# ffs_no_amp.net
KiCad netlist of a schematic drawn in EAGLE
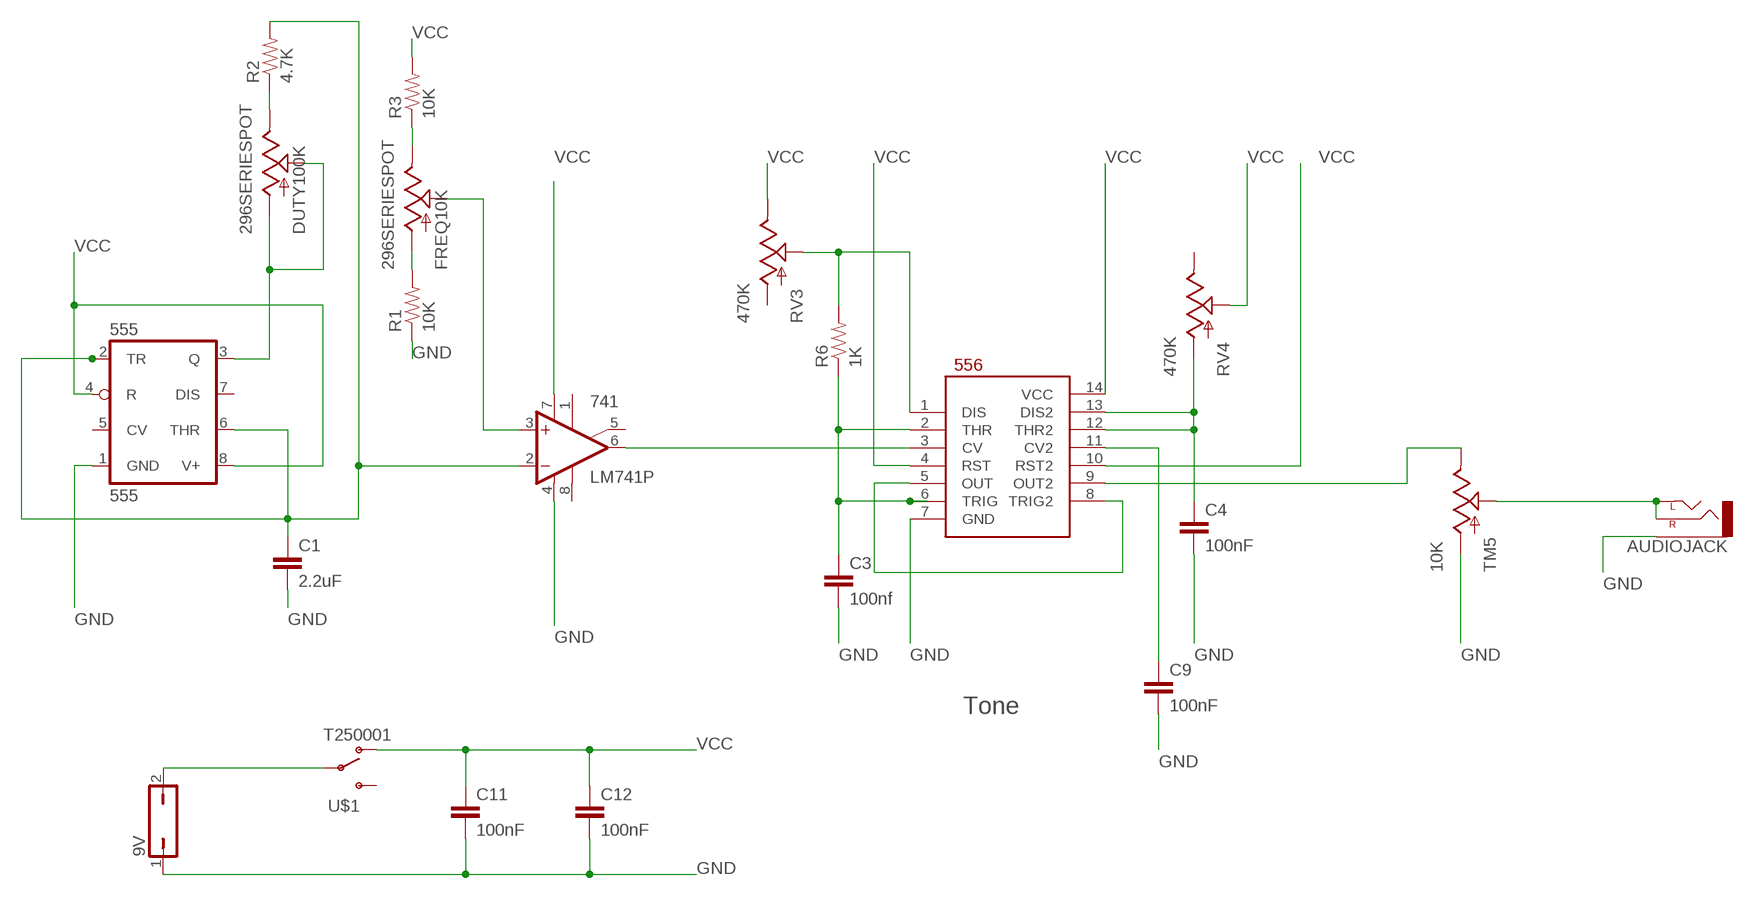
[diagram p0: schematic, sheet 1]

(export (version "E")
  (design (tool "Eeschema 10.0.6"))
  (components
    (comp (ref "9V")
      (value "JP1Q")
      (footprint "eagle-import:JP1")
      (libsource (lib "eagle-import") (part "JP1Q"))
    )
    (comp (ref "555")
      (value "555")
      (footprint "eagle-import:DIL08-ROUND")
      (libsource (lib "eagle-import") (part "555NLM"))
    )
    (comp (ref "556")
      (value "556")
      (footprint "eagle-import:DIL14")
      (libsource (lib "eagle-import") (part "556"))
    )
    (comp (ref "741")
      (value "LM741P")
      (footprint "eagle-import:DIL08")
      (libsource (lib "eagle-import") (part "741PLM"))
    )
    (comp (ref "AUDIOJACK")
      (value "AUDIO-JACKPTH")
      (footprint "eagle-import:AUDIO-JACK")
      (libsource (lib "eagle-import") (part "AUDIO-JACKPTH"))
    )
    (comp (ref "C1")
      (value "2.2uF")
      (footprint "eagle-import:CAP-PTH-5MM")
      (libsource (lib "eagle-import") (part "CAPPTH1"))
    )
    (comp (ref "C3")
      (value "100nf")
      (footprint "eagle-import:CAP-PTH-SMALL")
      (libsource (lib "eagle-import") (part "CAPPTH"))
    )
    (comp (ref "C4")
      (value "100nF")
      (footprint "eagle-import:CAP-PTH-SMALL")
      (libsource (lib "eagle-import") (part "CAPPTH"))
    )
    (comp (ref "C9")
      (value "100nF")
      (footprint "eagle-import:CAP-PTH-SMALL")
      (libsource (lib "eagle-import") (part "CAPPTH"))
    )
    (comp (ref "C11")
      (value "100nF")
      (footprint "eagle-import:CAP-PTH-SMALL")
      (libsource (lib "eagle-import") (part "CAPPTH"))
    )
    (comp (ref "C12")
      (value "100nF")
      (footprint "eagle-import:CAP-PTH-SMALL")
      (libsource (lib "eagle-import") (part "CAPPTH"))
    )
    (comp (ref "DUTY100K")
      (value "296SERIESPOT")
      (footprint "eagle-import:296SERIESPOT")
      (libsource (lib "eagle-import") (part "296SERIESPOT"))
    )
    (comp (ref "FREQ10K")
      (value "296SERIESPOT")
      (footprint "eagle-import:296SERIESPOT")
      (libsource (lib "eagle-import") (part "296SERIESPOT"))
    )
    (comp (ref "R1")
      (value "10K")
      (footprint "eagle-import:AXIAL-0.4")
      (libsource (lib "eagle-import") (part "SparkFun-Resistors_RESISTORPTH-1/4W"))
    )
    (comp (ref "R2")
      (value "4.7K")
      (footprint "eagle-import:AXIAL-0.4")
      (libsource (lib "eagle-import") (part "SparkFun-Resistors_RESISTORPTH-1/4W"))
    )
    (comp (ref "R3")
      (value "10K")
      (footprint "eagle-import:AXIAL-0.4")
      (libsource (lib "eagle-import") (part "SparkFun-Resistors_RESISTORPTH-1/4W"))
    )
    (comp (ref "R6")
      (value "1K")
      (footprint "eagle-import:AXIAL-0.4")
      (libsource (lib "eagle-import") (part "RESISTORPTH-1/4W"))
    )
    (comp (ref "RV3")
      (value "470K")
      (footprint "eagle-import:296SERIESPOT")
      (libsource (lib "eagle-import") (part "296SERIESPOT"))
    )
    (comp (ref "RV4")
      (value "470K")
      (footprint "eagle-import:296SERIESPOT")
      (libsource (lib "eagle-import") (part "296SERIESPOT"))
    )
    (comp (ref "TM5")
      (value "10K")
      (footprint "eagle-import:296SERIESPOT")
      (libsource (lib "eagle-import") (part "296SERIESPOT"))
    )
    (comp (ref "U$1")
      (value "T250001")
      (footprint "eagle-import:T250001")
      (libsource (lib "eagle-import") (part "T250001"))
    )
  )
  (nets
    (net (code "1") (name "/GND") (class "Default")
      (node (ref "555") (pin "1") (pinfunction "GND_1") (pintype "power_in"))
      (node (ref "556") (pin "7") (pinfunction "GND_7") (pintype "bidirectional"))
      (node (ref "741") (pin "4") (pinfunction "V-_4") (pintype "power_in"))
      (node (ref "9V") (pin "1") (pinfunction "1_1") (pintype "passive"))
      (node (ref "AUDIOJACK") (pin "SLEEVE") (pinfunction "SLEEVE_SLEEVE") (pintype "bidirectional"))
      (node (ref "C1") (pin "2") (pinfunction "2_2") (pintype "passive"))
      (node (ref "C11") (pin "2") (pinfunction "2_2") (pintype "passive"))
      (node (ref "C12") (pin "2") (pinfunction "2_2") (pintype "passive"))
      (node (ref "C3") (pin "2") (pinfunction "2_2") (pintype "passive"))
      (node (ref "C4") (pin "2") (pinfunction "2_2") (pintype "passive"))
      (node (ref "C9") (pin "2") (pinfunction "2_2") (pintype "passive"))
      (node (ref "R1") (pin "P$1") (pinfunction "1_P$1") (pintype "passive"))
      (node (ref "TM5") (pin "PIN1") (pinfunction "A_PIN1") (pintype "passive"))
    )
    (net (code "2") (name "/VCC") (class "Default")
      (node (ref "555") (pin "4") (pinfunction "R_4") (pintype "input"))
      (node (ref "555") (pin "8") (pinfunction "V+_8") (pintype "power_in"))
      (node (ref "556") (pin "10") (pinfunction "RST2_10") (pintype "bidirectional"))
      (node (ref "556") (pin "14") (pinfunction "VCC_14") (pintype "bidirectional"))
      (node (ref "556") (pin "4") (pinfunction "RST_4") (pintype "bidirectional"))
      (node (ref "741") (pin "7") (pinfunction "V+_7") (pintype "power_in"))
      (node (ref "C11") (pin "1") (pinfunction "1_1") (pintype "passive"))
      (node (ref "C12") (pin "1") (pinfunction "1_1") (pintype "passive"))
      (node (ref "R3") (pin "P$2") (pinfunction "2_P$2") (pintype "passive"))
      (node (ref "RV3") (pin "PIN3") (pinfunction "E_PIN3") (pintype "passive"))
      (node (ref "RV4") (pin "PIN2") (pinfunction "S_PIN2") (pintype "passive"))
      (node (ref "U$1") (pin "4") (pinfunction "O_4") (pintype "passive"))
    )
    (net (code "3") (name "Net-(555-Q)") (class "Default")
      (node (ref "555") (pin "3") (pinfunction "Q_3") (pintype "output"))
      (node (ref "DUTY100K") (pin "PIN1") (pinfunction "A_PIN1") (pintype "passive"))
      (node (ref "DUTY100K") (pin "PIN2") (pinfunction "S_PIN2") (pintype "passive"))
    )
    (net (code "4") (name "Net-(555-THR)") (class "Default")
      (node (ref "555") (pin "2") (pinfunction "TR_2") (pintype "input"))
      (node (ref "555") (pin "6") (pinfunction "THR_6") (pintype "input"))
      (node (ref "741") (pin "2") (pinfunction "-IN_2") (pintype "input"))
      (node (ref "C1") (pin "1") (pinfunction "1_1") (pintype "passive"))
      (node (ref "R2") (pin "P$2") (pinfunction "2_P$2") (pintype "passive"))
    )
    (net (code "5") (name "Net-(556-CV)") (class "Default")
      (node (ref "556") (pin "3") (pinfunction "CV_3") (pintype "bidirectional"))
      (node (ref "741") (pin "6") (pinfunction "OUT_6") (pintype "output"))
    )
    (net (code "6") (name "Net-(556-CV2)") (class "Default")
      (node (ref "556") (pin "11") (pinfunction "CV2_11") (pintype "bidirectional"))
      (node (ref "C9") (pin "1") (pinfunction "1_1") (pintype "passive"))
    )
    (net (code "7") (name "Net-(556-DIS)") (class "Default")
      (node (ref "556") (pin "1") (pinfunction "DIS_1") (pintype "bidirectional"))
      (node (ref "R6") (pin "P$2") (pinfunction "2_P$2") (pintype "passive"))
      (node (ref "RV3") (pin "PIN2") (pinfunction "S_PIN2") (pintype "passive"))
    )
    (net (code "8") (name "Net-(556-DIS2)") (class "Default")
      (node (ref "556") (pin "12") (pinfunction "THR2_12") (pintype "bidirectional"))
      (node (ref "556") (pin "13") (pinfunction "DIS2_13") (pintype "bidirectional"))
      (node (ref "C4") (pin "1") (pinfunction "1_1") (pintype "passive"))
      (node (ref "RV4") (pin "PIN1") (pinfunction "A_PIN1") (pintype "passive"))
    )
    (net (code "9") (name "Net-(556-OUT)") (class "Default")
      (node (ref "556") (pin "5") (pinfunction "OUT_5") (pintype "bidirectional"))
      (node (ref "556") (pin "8") (pinfunction "TRIG2_8") (pintype "bidirectional"))
    )
    (net (code "10") (name "Net-(556-OUT2)") (class "Default")
      (node (ref "556") (pin "9") (pinfunction "OUT2_9") (pintype "bidirectional"))
      (node (ref "TM5") (pin "PIN3") (pinfunction "E_PIN3") (pintype "passive"))
    )
    (net (code "11") (name "Net-(556-THR)") (class "Default")
      (node (ref "556") (pin "2") (pinfunction "THR_2") (pintype "bidirectional"))
      (node (ref "556") (pin "6") (pinfunction "TRIG_6") (pintype "bidirectional"))
      (node (ref "C3") (pin "1") (pinfunction "1_1") (pintype "passive"))
      (node (ref "R6") (pin "P$1") (pinfunction "1_P$1") (pintype "passive"))
    )
    (net (code "12") (name "Net-(741-+IN)") (class "Default")
      (node (ref "741") (pin "3") (pinfunction "+IN_3") (pintype "input"))
      (node (ref "FREQ10K") (pin "PIN2") (pinfunction "S_PIN2") (pintype "passive"))
    )
    (net (code "13") (name "Net-(AUDIOJACK-LEFT)") (class "Default")
      (node (ref "AUDIOJACK") (pin "RING") (pinfunction "RIGHT_RING") (pintype "bidirectional"))
      (node (ref "AUDIOJACK") (pin "TIP") (pinfunction "LEFT_TIP") (pintype "bidirectional"))
      (node (ref "TM5") (pin "PIN2") (pinfunction "S_PIN2") (pintype "passive"))
    )
    (net (code "14") (name "Net-(DUTY100K-E)") (class "Default")
      (node (ref "DUTY100K") (pin "PIN3") (pinfunction "E_PIN3") (pintype "passive"))
      (node (ref "R2") (pin "P$1") (pinfunction "1_P$1") (pintype "passive"))
    )
    (net (code "15") (name "Net-(FREQ10K-A)") (class "Default")
      (node (ref "FREQ10K") (pin "PIN1") (pinfunction "A_PIN1") (pintype "passive"))
      (node (ref "R1") (pin "P$2") (pinfunction "2_P$2") (pintype "passive"))
    )
    (net (code "16") (name "Net-(FREQ10K-E)") (class "Default")
      (node (ref "FREQ10K") (pin "PIN3") (pinfunction "E_PIN3") (pintype "passive"))
      (node (ref "R3") (pin "P$1") (pinfunction "1_P$1") (pintype "passive"))
    )
    (net (code "17") (name "Net-(U$1-P)") (class "Default")
      (node (ref "9V") (pin "2") (pinfunction "2_2") (pintype "passive"))
      (node (ref "U$1") (pin "5") (pinfunction "P_5") (pintype "passive"))
    )
    (net (code "18") (name "unconnected-(555-CV-Pad5)") (class "Default")
      (node (ref "555") (pin "5") (pinfunction "CV_5") (pintype "input"))
    )
    (net (code "19") (name "unconnected-(555-DIS-Pad7)") (class "Default")
      (node (ref "555") (pin "7") (pinfunction "DIS_7") (pintype "input"))
    )
    (net (code "20") (name "unconnected-(741-ON1-Pad1)") (class "Default")
      (node (ref "741") (pin "1") (pinfunction "ON1_1") (pintype "passive"))
    )
    (net (code "21") (name "unconnected-(741-ON2-Pad5)") (class "Default")
      (node (ref "741") (pin "5") (pinfunction "ON2_5") (pintype "passive"))
    )
    (net (code "22") (name "unconnected-(741-OPT-Pad8)") (class "Default")
      (node (ref "741") (pin "8") (pinfunction "OPT_8") (pintype "passive"))
    )
    (net (code "23") (name "unconnected-(RV3-A-PadPIN1)") (class "Default")
      (node (ref "RV3") (pin "PIN1") (pinfunction "A_PIN1") (pintype "passive"))
    )
    (net (code "24") (name "unconnected-(RV4-E-PadPIN3)") (class "Default")
      (node (ref "RV4") (pin "PIN3") (pinfunction "E_PIN3") (pintype "passive"))
    )
    (net (code "25") (name "unconnected-(U$1-S-Pad6)") (class "Default")
      (node (ref "U$1") (pin "6") (pinfunction "S_6") (pintype "passive"))
    )
  )
)
